# SmartSwitch_V1_2.net
KiCad netlist of a schematic drawn in EAGLE
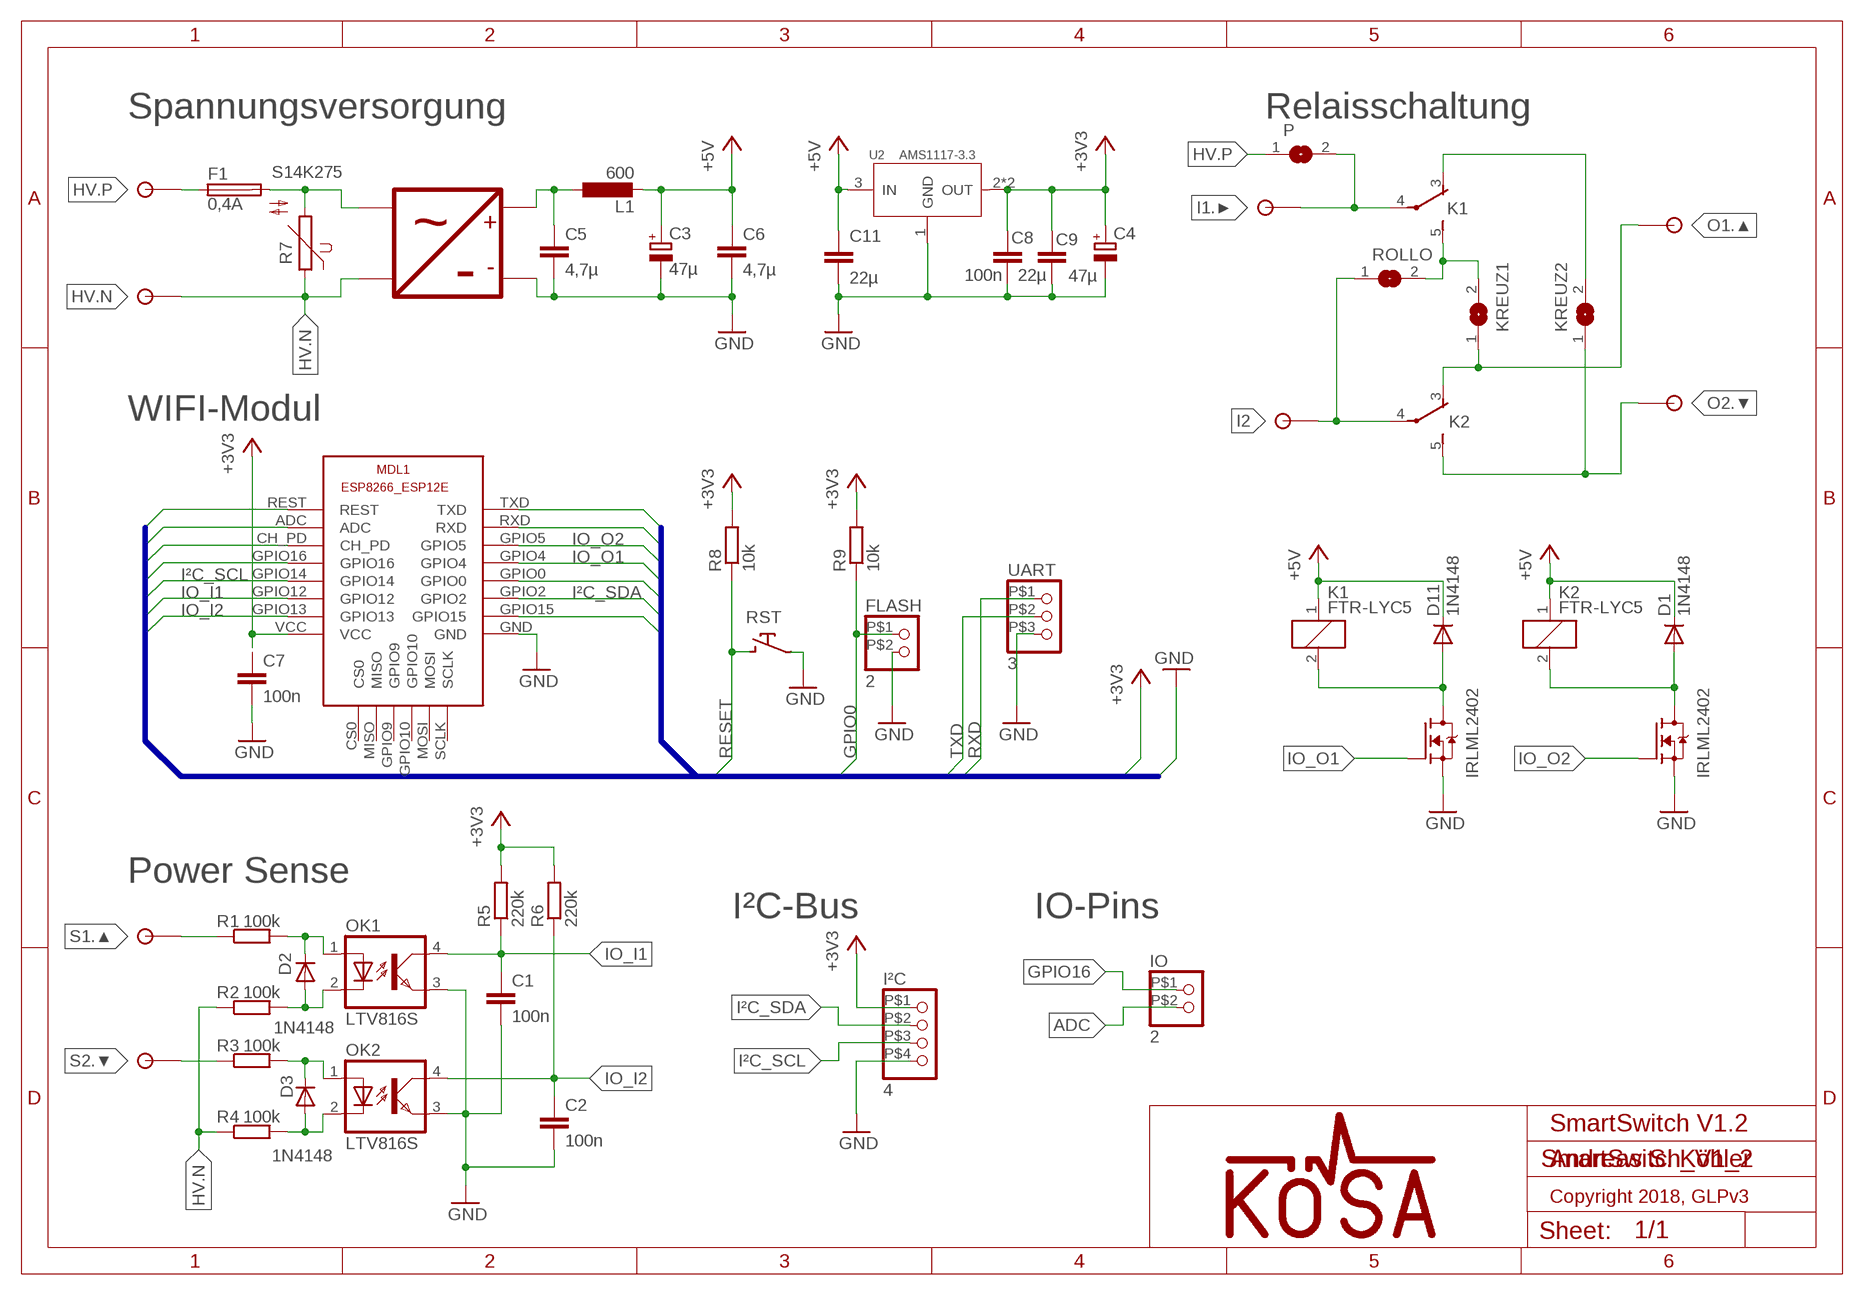
[diagram p0: schematic, sheet 1]

(export (version "E")
  (design (tool "Eeschema 10.0.6"))
  (components
    (comp (ref "C1")
      (value "100n")
      (footprint "eagle-import:C0805")
      (libsource (lib "eagle-import") (part "C-EUC0805"))
    )
    (comp (ref "C2")
      (value "100n")
      (footprint "eagle-import:C0805")
      (libsource (lib "eagle-import") (part "C-EUC0805"))
    )
    (comp (ref "C3")
      (value "47µ")
      (footprint "eagle-import:E2-5")
      (libsource (lib "eagle-import") (part "CPOL-EUE2-5"))
    )
    (comp (ref "C4")
      (value "47µ")
      (footprint "eagle-import:E2-5")
      (libsource (lib "eagle-import") (part "CPOL-EUE2-5"))
    )
    (comp (ref "C5")
      (value "4,7µ")
      (footprint "eagle-import:C0805")
      (libsource (lib "eagle-import") (part "C-EUC0805"))
    )
    (comp (ref "C6")
      (value "4,7µ")
      (footprint "eagle-import:C0805")
      (libsource (lib "eagle-import") (part "C-EUC0805"))
    )
    (comp (ref "C7")
      (value "100n")
      (footprint "eagle-import:C0805")
      (libsource (lib "eagle-import") (part "C-EUC0805"))
    )
    (comp (ref "C8")
      (value "100n")
      (footprint "eagle-import:C0805")
      (libsource (lib "eagle-import") (part "C-EUC0805"))
    )
    (comp (ref "C9")
      (value "22µ")
      (footprint "eagle-import:C0805")
      (libsource (lib "eagle-import") (part "C-EUC0805"))
    )
    (comp (ref "C11")
      (value "22µ")
      (footprint "eagle-import:C0805")
      (libsource (lib "eagle-import") (part "C-EUC0805"))
    )
    (comp (ref "D1")
      (value "1N4148")
      (footprint "eagle-import:SOD323-W")
      (libsource (lib "eagle-import") (part "DIODE-SOD323-W"))
    )
    (comp (ref "D2")
      (value "1N4148")
      (footprint "eagle-import:SOD323-W")
      (libsource (lib "eagle-import") (part "DIODE-SOD323-W"))
    )
    (comp (ref "D3")
      (value "1N4148")
      (footprint "eagle-import:SOD323-W")
      (libsource (lib "eagle-import") (part "DIODE-SOD323-W"))
    )
    (comp (ref "D11")
      (value "1N4148")
      (footprint "eagle-import:SOD323-W")
      (libsource (lib "eagle-import") (part "DIODE-SOD323-W"))
    )
    (comp (ref "F1")
      (value "0,4A")
      (footprint "eagle-import:SMD_FUSE_HOLDER")
      (libsource (lib "eagle-import") (part "SMD_FUSE_HOLDER"))
    )
    (comp (ref "FLASH")
      (value "2")
      (footprint "eagle-import:1X02_SMALL")
      (libsource (lib "eagle-import") (part "PINHD-1X2SMALL"))
    )
    (comp (ref "IO")
      (value "2")
      (footprint "eagle-import:1X02_SMALL")
      (libsource (lib "eagle-import") (part "PINHD-1X2SMALL"))
    )
    (comp (ref "I²C")
      (value "4")
      (footprint "eagle-import:1X04_SMALL")
      (libsource (lib "eagle-import") (part "PINHD-1X4SMALL"))
    )
    (comp (ref "K1")
      (value "FTR-LYC5")
      (footprint "eagle-import:FTR-LYC")
      (libsource (lib "eagle-import") (part "FTR-LYC5"))
    )
    (comp (ref "K2")
      (value "FTR-LYC5")
      (footprint "eagle-import:FTR-LYC")
      (libsource (lib "eagle-import") (part "FTR-LYC5"))
    )
    (comp (ref "KREUZ1")
      (value "SJW")
      (footprint "eagle-import:SJW")
      (libsource (lib "eagle-import") (part "SJW"))
    )
    (comp (ref "KREUZ2")
      (value "SJW")
      (footprint "eagle-import:SJW")
      (libsource (lib "eagle-import") (part "SJW"))
    )
    (comp (ref "L1")
      (value "600")
      (footprint "eagle-import:L3225P")
      (libsource (lib "eagle-import") (part "L-EUL3225P"))
    )
    (comp (ref "MDL1")
      (value "1")
      (footprint "eagle-import:ESP8266-ESP12E")
      (libsource (lib "eagle-import") (part "ESP8266-12EESP8266-ESP12E"))
    )
    (comp (ref "OK1")
      (value "LTV816S")
      (footprint "eagle-import:SMD4")
      (libsource (lib "eagle-import") (part "LTV816S"))
    )
    (comp (ref "OK2")
      (value "LTV816S")
      (footprint "eagle-import:SMD4")
      (libsource (lib "eagle-import") (part "LTV816S"))
    )
    (comp (ref "P")
      (value "SJW")
      (footprint "eagle-import:SJW")
      (libsource (lib "eagle-import") (part "SJW"))
    )
    (comp (ref "R1")
      (value "100k")
      (footprint "eagle-import:R1206")
      (libsource (lib "eagle-import") (part "R-EU_R1206"))
    )
    (comp (ref "R2")
      (value "100k")
      (footprint "eagle-import:R1206")
      (libsource (lib "eagle-import") (part "R-EU_R1206"))
    )
    (comp (ref "R3")
      (value "100k")
      (footprint "eagle-import:R1206")
      (libsource (lib "eagle-import") (part "R-EU_R1206"))
    )
    (comp (ref "R4")
      (value "100k")
      (footprint "eagle-import:R1206")
      (libsource (lib "eagle-import") (part "R-EU_R1206"))
    )
    (comp (ref "R5")
      (value "220k")
      (footprint "eagle-import:R1206")
      (libsource (lib "eagle-import") (part "R-EU_R1206"))
    )
    (comp (ref "R6")
      (value "220k")
      (footprint "eagle-import:R1206")
      (libsource (lib "eagle-import") (part "R-EU_R1206"))
    )
    (comp (ref "R7")
      (value "S14K275")
      (footprint "eagle-import:S14K275_")
      (libsource (lib "eagle-import") (part "S14K275GESPIEGELT"))
    )
    (comp (ref "R8")
      (value "10k")
      (footprint "eagle-import:R1206")
      (libsource (lib "eagle-import") (part "R-EU_R1206"))
    )
    (comp (ref "R9")
      (value "10k")
      (footprint "eagle-import:R1206")
      (libsource (lib "eagle-import") (part "R-EU_R1206"))
    )
    (comp (ref "ROLLO")
      (value "SJW")
      (footprint "eagle-import:SJW")
      (libsource (lib "eagle-import") (part "SJW"))
    )
    (comp (ref "RST")
      (value "SMD-TASTER_REICHELT_KMR_231_G_LFS")
      (footprint "eagle-import:SMD-TASTER_REICHELT_KMR_231_G_LFS")
      (libsource (lib "eagle-import") (part "SMD-TASTER_REICHELT_KMR_231_G_LFS"))
    )
    (comp (ref "U$1")
      (value "HLK-PM01")
      (footprint "eagle-import:HLK-PM01")
      (libsource (lib "eagle-import") (part "HLK-PM01"))
    )
    (comp (ref "U$2")
      (value "RND_205-00276")
      (footprint "eagle-import:RND205-00276")
      (libsource (lib "eagle-import") (part "RND_205-00276"))
    )
    (comp (ref "U$3")
      (value "RND_205-00276")
      (footprint "eagle-import:RND205-00276")
      (libsource (lib "eagle-import") (part "RND_205-00276"))
    )
    (comp (ref "U$4")
      (value "RND_205-00276")
      (footprint "eagle-import:RND205-00276")
      (libsource (lib "eagle-import") (part "RND_205-00276"))
    )
    (comp (ref "U$5")
      (value "RND_205-00276")
      (footprint "eagle-import:RND205-00276")
      (libsource (lib "eagle-import") (part "RND_205-00276"))
    )
    (comp (ref "U$7")
      (value "IRLML2402")
      (footprint "eagle-import:SOT23")
      (libsource (lib "eagle-import") (part "IRLML2502"))
    )
    (comp (ref "U$8")
      (value "IRLML2402")
      (footprint "eagle-import:SOT23")
      (libsource (lib "eagle-import") (part "IRLML2502"))
    )
    (comp (ref "U2")
      (value "AMS1117-3.3")
      (footprint "eagle-import:SOT-223")
      (fields (field (name "MPN") "CJT1117-3.3"))
      (libsource (lib "eagle-import") (part "PMIC-CJT1117-3.3(SOT223)"))
    )
    (comp (ref "UART")
      (value "3")
      (footprint "eagle-import:1X03_SMALL")
      (libsource (lib "eagle-import") (part "PINHD-1X3SMALL"))
    )
  )
  (nets
    (net (code "1") (name "+3V3") (class "Default")
      (node (ref "C4") (pin "+") (pinfunction "+_+") (pintype "passive"))
      (node (ref "C7") (pin "1") (pinfunction "1_1") (pintype "passive"))
      (node (ref "C8") (pin "1") (pinfunction "1_1") (pintype "passive"))
      (node (ref "C9") (pin "1") (pinfunction "1_1") (pintype "passive"))
      (node (ref "I²C") (pin "P$1") (pinfunction "1_P$1") (pintype "passive"))
      (node (ref "MDL1") (pin "CH_PD") (pinfunction "CH_PD_CH_PD") (pintype "bidirectional"))
      (node (ref "MDL1") (pin "VCC") (pinfunction "VCC_VCC") (pintype "bidirectional"))
      (node (ref "R5") (pin "2") (pinfunction "2_2") (pintype "passive"))
      (node (ref "R6") (pin "2") (pinfunction "2_2") (pintype "passive"))
      (node (ref "R8") (pin "2") (pinfunction "2_2") (pintype "passive"))
      (node (ref "R9") (pin "2") (pinfunction "2_2") (pintype "passive"))
      (node (ref "U2") (pin "2") (pinfunction "OUT_2") (pintype "bidirectional"))
      (node (ref "U2") (pin "TER") (pinfunction "OUT_TER") (pintype "bidirectional"))
    )
    (net (code "2") (name "+5V") (class "Default")
      (node (ref "C11") (pin "1") (pinfunction "1_1") (pintype "passive"))
      (node (ref "C3") (pin "+") (pinfunction "+_+") (pintype "passive"))
      (node (ref "C6") (pin "1") (pinfunction "1_1") (pintype "passive"))
      (node (ref "D1") (pin "C") (pinfunction "C_C") (pintype "passive"))
      (node (ref "D11") (pin "C") (pinfunction "C_C") (pintype "passive"))
      (node (ref "K1") (pin "1") (pinfunction "1_1") (pintype "passive"))
      (node (ref "K2") (pin "1") (pinfunction "1_1") (pintype "passive"))
      (node (ref "L1") (pin "2") (pinfunction "2_2") (pintype "passive"))
      (node (ref "U2") (pin "3") (pinfunction "IN_3") (pintype "bidirectional"))
    )
    (net (code "3") (name "/GPIO0") (class "Default")
      (node (ref "FLASH") (pin "P$1") (pinfunction "1_P$1") (pintype "passive"))
      (node (ref "MDL1") (pin "GPIO0") (pinfunction "GPIO0_GPIO0") (pintype "bidirectional"))
      (node (ref "R9") (pin "1") (pinfunction "1_1") (pintype "passive"))
    )
    (net (code "4") (name "/RESET") (class "Default")
      (node (ref "MDL1") (pin "REST") (pinfunction "REST_REST") (pintype "bidirectional"))
      (node (ref "R8") (pin "1") (pinfunction "1_1") (pintype "passive"))
      (node (ref "RST") (pin "2_1") (pinfunction "B_2_1") (pintype "bidirectional"))
      (node (ref "RST") (pin "2_2") (pinfunction "B_2_2") (pintype "bidirectional"))
    )
    (net (code "5") (name "/RXD") (class "Default")
      (node (ref "MDL1") (pin "RXD") (pinfunction "RXD_RXD") (pintype "bidirectional"))
      (node (ref "UART") (pin "P$1") (pinfunction "1_P$1") (pintype "passive"))
    )
    (net (code "6") (name "/TXD") (class "Default")
      (node (ref "MDL1") (pin "TXD") (pinfunction "TXD_TXD") (pintype "bidirectional"))
      (node (ref "UART") (pin "P$2") (pinfunction "2_P$2") (pintype "passive"))
    )
    (net (code "7") (name "ADC") (class "Default")
      (node (ref "IO") (pin "P$2") (pinfunction "2_P$2") (pintype "passive"))
      (node (ref "MDL1") (pin "ADC") (pinfunction "ADC_ADC") (pintype "bidirectional"))
    )
    (net (code "8") (name "GND") (class "Default")
      (node (ref "C1") (pin "2") (pinfunction "2_2") (pintype "passive"))
      (node (ref "C11") (pin "2") (pinfunction "2_2") (pintype "passive"))
      (node (ref "C2") (pin "2") (pinfunction "2_2") (pintype "passive"))
      (node (ref "C3") (pin "-") (pinfunction "-_-") (pintype "passive"))
      (node (ref "C4") (pin "-") (pinfunction "-_-") (pintype "passive"))
      (node (ref "C5") (pin "2") (pinfunction "2_2") (pintype "passive"))
      (node (ref "C6") (pin "2") (pinfunction "2_2") (pintype "passive"))
      (node (ref "C7") (pin "2") (pinfunction "2_2") (pintype "passive"))
      (node (ref "C8") (pin "2") (pinfunction "2_2") (pintype "passive"))
      (node (ref "C9") (pin "2") (pinfunction "2_2") (pintype "passive"))
      (node (ref "FLASH") (pin "P$2") (pinfunction "2_P$2") (pintype "passive"))
      (node (ref "I²C") (pin "P$4") (pinfunction "4_P$4") (pintype "passive"))
      (node (ref "MDL1") (pin "GND") (pinfunction "GND_GND") (pintype "bidirectional"))
      (node (ref "MDL1") (pin "GPIO15") (pinfunction "GPIO15_GPIO15") (pintype "bidirectional"))
      (node (ref "OK1") (pin "3") (pinfunction "EMIT_3") (pintype "passive"))
      (node (ref "OK2") (pin "3") (pinfunction "EMIT_3") (pintype "passive"))
      (node (ref "RST") (pin "1_1") (pinfunction "A_1_1") (pintype "bidirectional"))
      (node (ref "RST") (pin "1_2") (pinfunction "A_1_2") (pintype "bidirectional"))
      (node (ref "U$1") (pin "DC-") (pinfunction "DC-_DC-") (pintype "power_in"))
      (node (ref "U$7") (pin "2") (pinfunction "S_2") (pintype "passive"))
      (node (ref "U$8") (pin "2") (pinfunction "S_2") (pintype "passive"))
      (node (ref "U2") (pin "1") (pinfunction "GND_1") (pintype "bidirectional"))
      (node (ref "UART") (pin "P$3") (pinfunction "3_P$3") (pintype "passive"))
    )
    (net (code "9") (name "GPIO16") (class "Default")
      (node (ref "IO") (pin "P$1") (pinfunction "1_P$1") (pintype "passive"))
      (node (ref "MDL1") (pin "GPIO16") (pinfunction "GPIO16_GPIO16") (pintype "bidirectional"))
    )
    (net (code "10") (name "HV.N") (class "Default")
      (node (ref "R2") (pin "1") (pinfunction "1_1") (pintype "passive"))
      (node (ref "R4") (pin "1") (pinfunction "1_1") (pintype "passive"))
      (node (ref "R7") (pin "1") (pinfunction "1_1") (pintype "passive"))
      (node (ref "U$1") (pin "AC2") (pinfunction "AC2_AC2") (pintype "power_in"))
      (node (ref "U$2") (pin "P$2") (pinfunction "P$1_P$2") (pintype "bidirectional"))
    )
    (net (code "11") (name "HV.P") (class "Default")
      (node (ref "F1") (pin "P$1") (pinfunction "1_P$1") (pintype "passive"))
      (node (ref "P") (pin "1") (pinfunction "1_1") (pintype "passive"))
      (node (ref "U$2") (pin "P$1") (pinfunction "P$1_P$1") (pintype "bidirectional"))
    )
    (net (code "12") (name "I1.►") (class "Default")
      (node (ref "K1") (pin "4") (pinfunction "P_4") (pintype "passive"))
      (node (ref "P") (pin "2") (pinfunction "2_2") (pintype "passive"))
      (node (ref "U$4") (pin "P$1") (pinfunction "P$1_P$1") (pintype "bidirectional"))
    )
    (net (code "13") (name "I2") (class "Default")
      (node (ref "K2") (pin "4") (pinfunction "P_4") (pintype "passive"))
      (node (ref "ROLLO") (pin "1") (pinfunction "1_1") (pintype "passive"))
      (node (ref "U$3") (pin "P$1") (pinfunction "P$1_P$1") (pintype "bidirectional"))
    )
    (net (code "14") (name "IO_I1") (class "Default")
      (node (ref "C1") (pin "1") (pinfunction "1_1") (pintype "passive"))
      (node (ref "MDL1") (pin "GPIO12") (pinfunction "GPIO12_GPIO12") (pintype "bidirectional"))
      (node (ref "OK1") (pin "4") (pinfunction "COL_4") (pintype "passive"))
      (node (ref "R5") (pin "1") (pinfunction "1_1") (pintype "passive"))
    )
    (net (code "15") (name "IO_I2") (class "Default")
      (node (ref "C2") (pin "1") (pinfunction "1_1") (pintype "passive"))
      (node (ref "MDL1") (pin "GPIO13") (pinfunction "GPIO13_GPIO13") (pintype "bidirectional"))
      (node (ref "OK2") (pin "4") (pinfunction "COL_4") (pintype "passive"))
      (node (ref "R6") (pin "1") (pinfunction "1_1") (pintype "passive"))
    )
    (net (code "16") (name "IO_O1") (class "Default")
      (node (ref "MDL1") (pin "GPIO4") (pinfunction "GPIO4_GPIO4") (pintype "bidirectional"))
      (node (ref "U$7") (pin "1") (pinfunction "G_1") (pintype "passive"))
    )
    (net (code "17") (name "IO_O2") (class "Default")
      (node (ref "MDL1") (pin "GPIO5") (pinfunction "GPIO5_GPIO5") (pintype "bidirectional"))
      (node (ref "U$8") (pin "1") (pinfunction "G_1") (pintype "passive"))
    )
    (net (code "18") (name "I²C_SCL") (class "Default")
      (node (ref "I²C") (pin "P$3") (pinfunction "3_P$3") (pintype "passive"))
      (node (ref "MDL1") (pin "GPIO14") (pinfunction "GPIO14_GPIO14") (pintype "bidirectional"))
    )
    (net (code "19") (name "I²C_SDA") (class "Default")
      (node (ref "I²C") (pin "P$2") (pinfunction "2_P$2") (pintype "passive"))
      (node (ref "MDL1") (pin "GPIO2") (pinfunction "GPIO2_GPIO2") (pintype "bidirectional"))
    )
    (net (code "20") (name "Net-(C5-Pad1)") (class "Default")
      (node (ref "C5") (pin "1") (pinfunction "1_1") (pintype "passive"))
      (node (ref "L1") (pin "1") (pinfunction "1_1") (pintype "passive"))
      (node (ref "U$1") (pin "DC+") (pinfunction "DC+_DC+") (pintype "power_in"))
    )
    (net (code "21") (name "Net-(F1-2)") (class "Default")
      (node (ref "F1") (pin "P$2") (pinfunction "2_P$2") (pintype "passive"))
      (node (ref "R7") (pin "2") (pinfunction "2_2") (pintype "passive"))
      (node (ref "U$1") (pin "AC1") (pinfunction "AC1_AC1") (pintype "power_in"))
    )
    (net (code "22") (name "Net-(K1A-O)") (class "Default")
      (node (ref "K1") (pin "3") (pinfunction "O_3") (pintype "passive"))
      (node (ref "KREUZ2") (pin "2") (pinfunction "2_2") (pintype "passive"))
    )
    (net (code "23") (name "Net-(K1A-S)") (class "Default")
      (node (ref "K1") (pin "5") (pinfunction "S_5") (pintype "passive"))
      (node (ref "KREUZ1") (pin "2") (pinfunction "2_2") (pintype "passive"))
      (node (ref "ROLLO") (pin "2") (pinfunction "2_2") (pintype "passive"))
    )
    (net (code "24") (name "Net-(OK1-A)") (class "Default")
      (node (ref "D2") (pin "C") (pinfunction "C_C") (pintype "passive"))
      (node (ref "OK1") (pin "1") (pinfunction "A_1") (pintype "passive"))
      (node (ref "R1") (pin "2") (pinfunction "2_2") (pintype "passive"))
    )
    (net (code "25") (name "Net-(OK1-C)") (class "Default")
      (node (ref "D2") (pin "A") (pinfunction "A_A") (pintype "passive"))
      (node (ref "OK1") (pin "2") (pinfunction "C_2") (pintype "passive"))
      (node (ref "R2") (pin "2") (pinfunction "2_2") (pintype "passive"))
    )
    (net (code "26") (name "Net-(OK2-A)") (class "Default")
      (node (ref "D3") (pin "C") (pinfunction "C_C") (pintype "passive"))
      (node (ref "OK2") (pin "1") (pinfunction "A_1") (pintype "passive"))
      (node (ref "R3") (pin "2") (pinfunction "2_2") (pintype "passive"))
    )
    (net (code "27") (name "Net-(OK2-C)") (class "Default")
      (node (ref "D3") (pin "A") (pinfunction "A_A") (pintype "passive"))
      (node (ref "OK2") (pin "2") (pinfunction "C_2") (pintype "passive"))
      (node (ref "R4") (pin "2") (pinfunction "2_2") (pintype "passive"))
    )
    (net (code "28") (name "Net-(U$7-D)") (class "Default")
      (node (ref "D11") (pin "A") (pinfunction "A_A") (pintype "passive"))
      (node (ref "K1") (pin "2") (pinfunction "2_2") (pintype "passive"))
      (node (ref "U$7") (pin "3") (pinfunction "D_3") (pintype "passive"))
    )
    (net (code "29") (name "Net-(U$8-D)") (class "Default")
      (node (ref "D1") (pin "A") (pinfunction "A_A") (pintype "passive"))
      (node (ref "K2") (pin "2") (pinfunction "2_2") (pintype "passive"))
      (node (ref "U$8") (pin "3") (pinfunction "D_3") (pintype "passive"))
    )
    (net (code "30") (name "O1.▲") (class "Default")
      (node (ref "K2") (pin "3") (pinfunction "O_3") (pintype "passive"))
      (node (ref "KREUZ1") (pin "1") (pinfunction "1_1") (pintype "passive"))
      (node (ref "U$3") (pin "P$2") (pinfunction "P$1_P$2") (pintype "bidirectional"))
    )
    (net (code "31") (name "O2.▼") (class "Default")
      (node (ref "K2") (pin "5") (pinfunction "S_5") (pintype "passive"))
      (node (ref "KREUZ2") (pin "1") (pinfunction "1_1") (pintype "passive"))
      (node (ref "U$4") (pin "P$2") (pinfunction "P$1_P$2") (pintype "bidirectional"))
    )
    (net (code "32") (name "S1.▲") (class "Default")
      (node (ref "R1") (pin "1") (pinfunction "1_1") (pintype "passive"))
      (node (ref "U$5") (pin "P$2") (pinfunction "P$1_P$2") (pintype "bidirectional"))
    )
    (net (code "33") (name "S2.▼") (class "Default")
      (node (ref "R3") (pin "1") (pinfunction "1_1") (pintype "passive"))
      (node (ref "U$5") (pin "P$1") (pinfunction "P$1_P$1") (pintype "bidirectional"))
    )
    (net (code "34") (name "unconnected-(MDL1-PadCS0)") (class "Default")
      (node (ref "MDL1") (pin "CS0") (pinfunction "CS0_CS0") (pintype "bidirectional"))
    )
    (net (code "35") (name "unconnected-(MDL1-PadGPIO9)") (class "Default")
      (node (ref "MDL1") (pin "GPIO9") (pinfunction "GPIO9_GPIO9") (pintype "bidirectional"))
    )
    (net (code "36") (name "unconnected-(MDL1-PadGPIO10)") (class "Default")
      (node (ref "MDL1") (pin "GPIO10") (pinfunction "GPIO10_GPIO10") (pintype "bidirectional"))
    )
    (net (code "37") (name "unconnected-(MDL1-PadMISO)") (class "Default")
      (node (ref "MDL1") (pin "MISO") (pinfunction "MISO_MISO") (pintype "bidirectional"))
    )
    (net (code "38") (name "unconnected-(MDL1-PadMOSI)") (class "Default")
      (node (ref "MDL1") (pin "MOSI") (pinfunction "MOSI_MOSI") (pintype "bidirectional"))
    )
    (net (code "39") (name "unconnected-(MDL1-PadSCLK)") (class "Default")
      (node (ref "MDL1") (pin "SCLK") (pinfunction "SCLK_SCLK") (pintype "bidirectional"))
    )
  )
)
